# DRV8301_inverter.net
KiCad netlist of a schematic drawn in Altium Designer
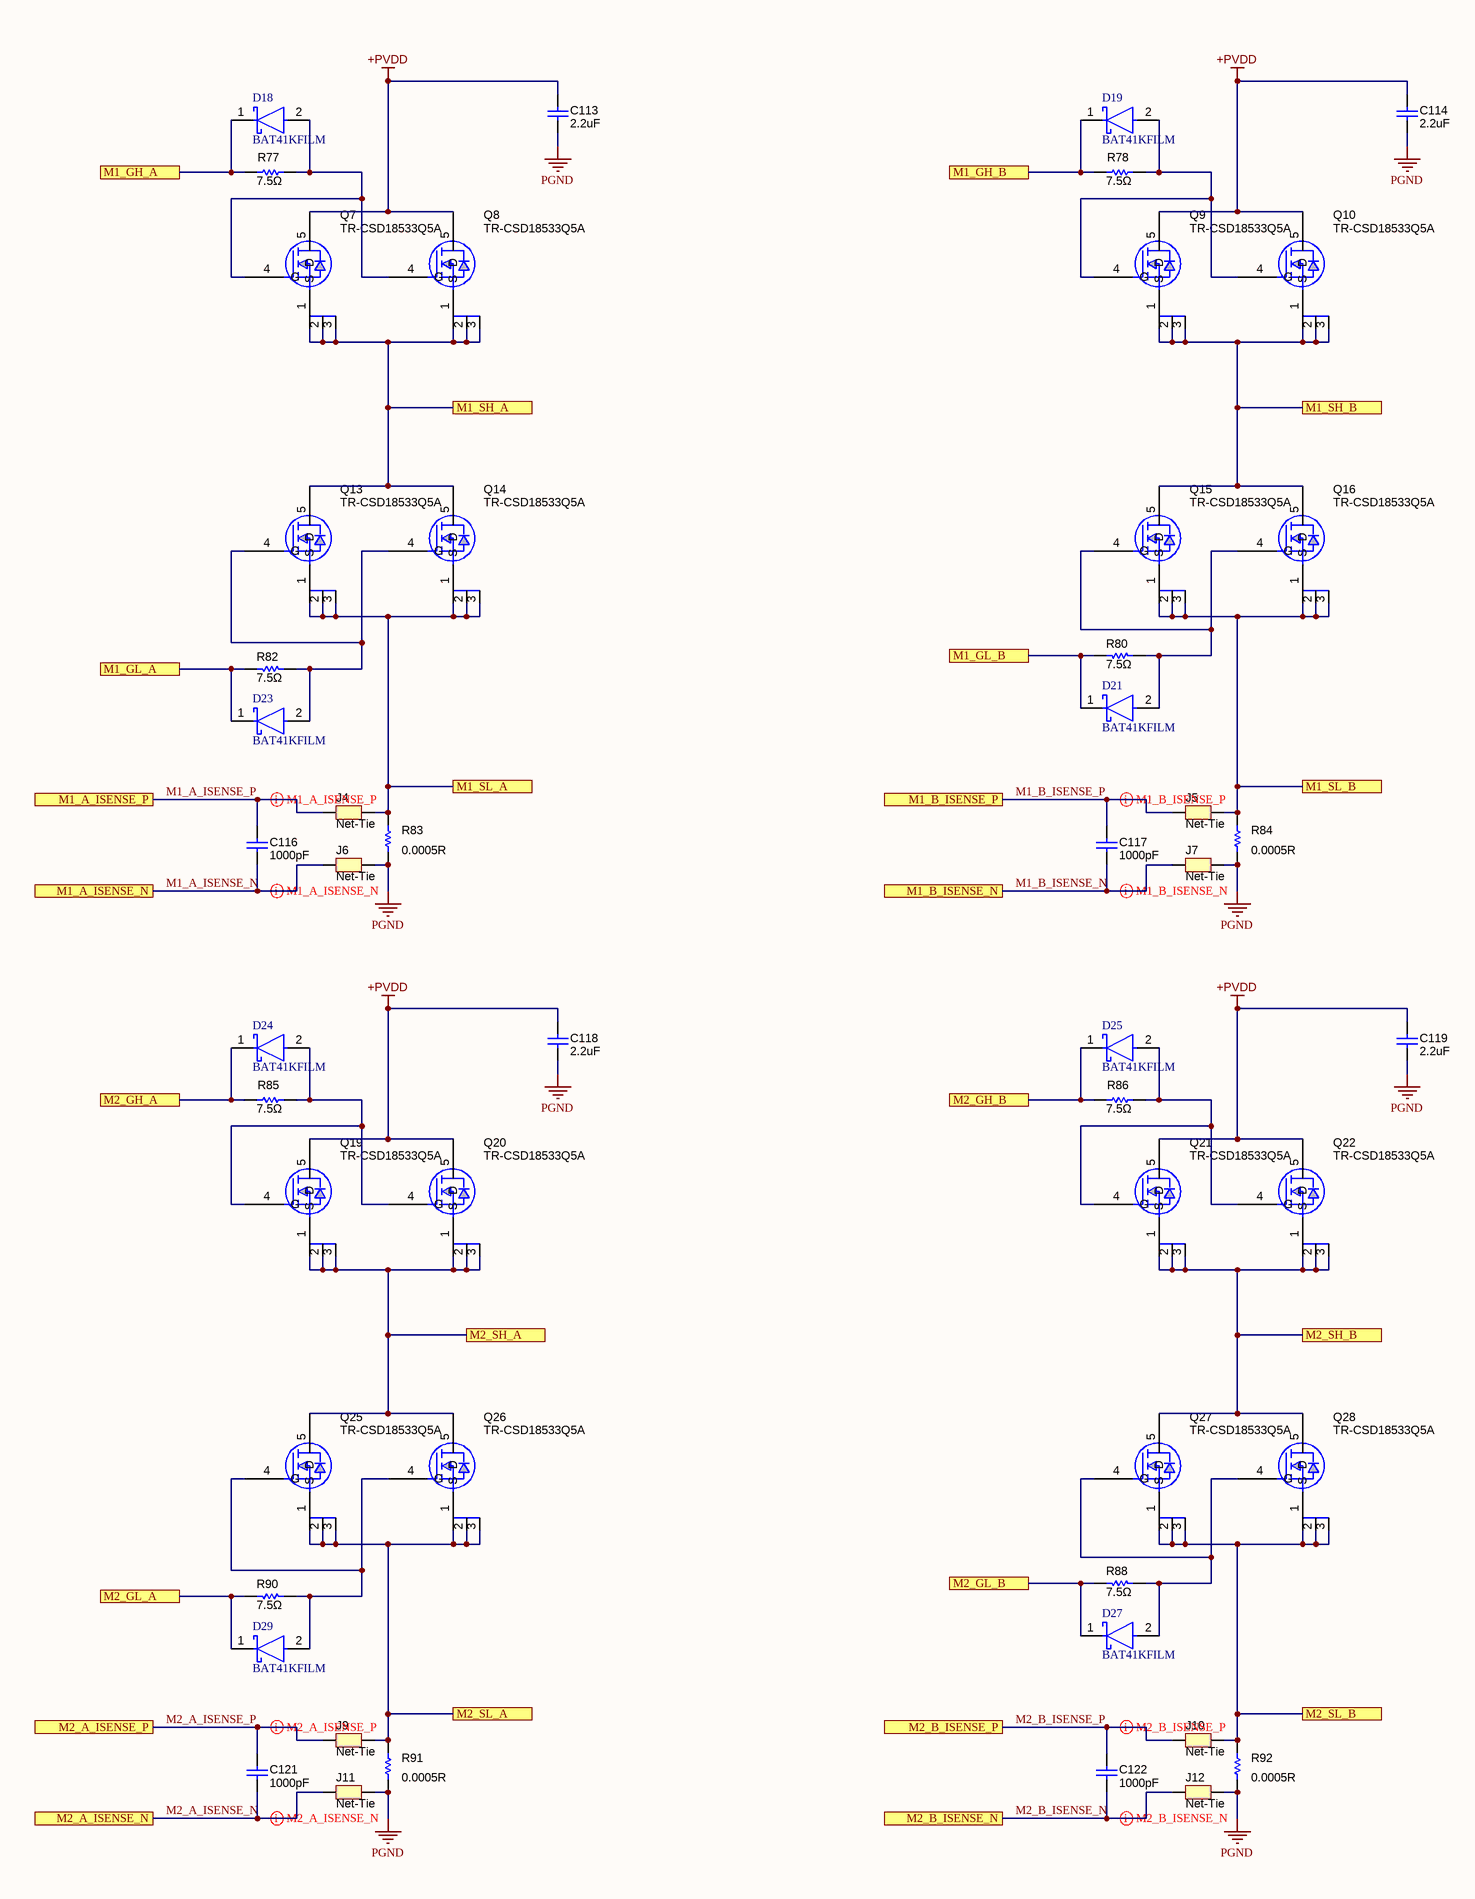
[diagram p0: DRV8301_inverter.SchDoc, left]
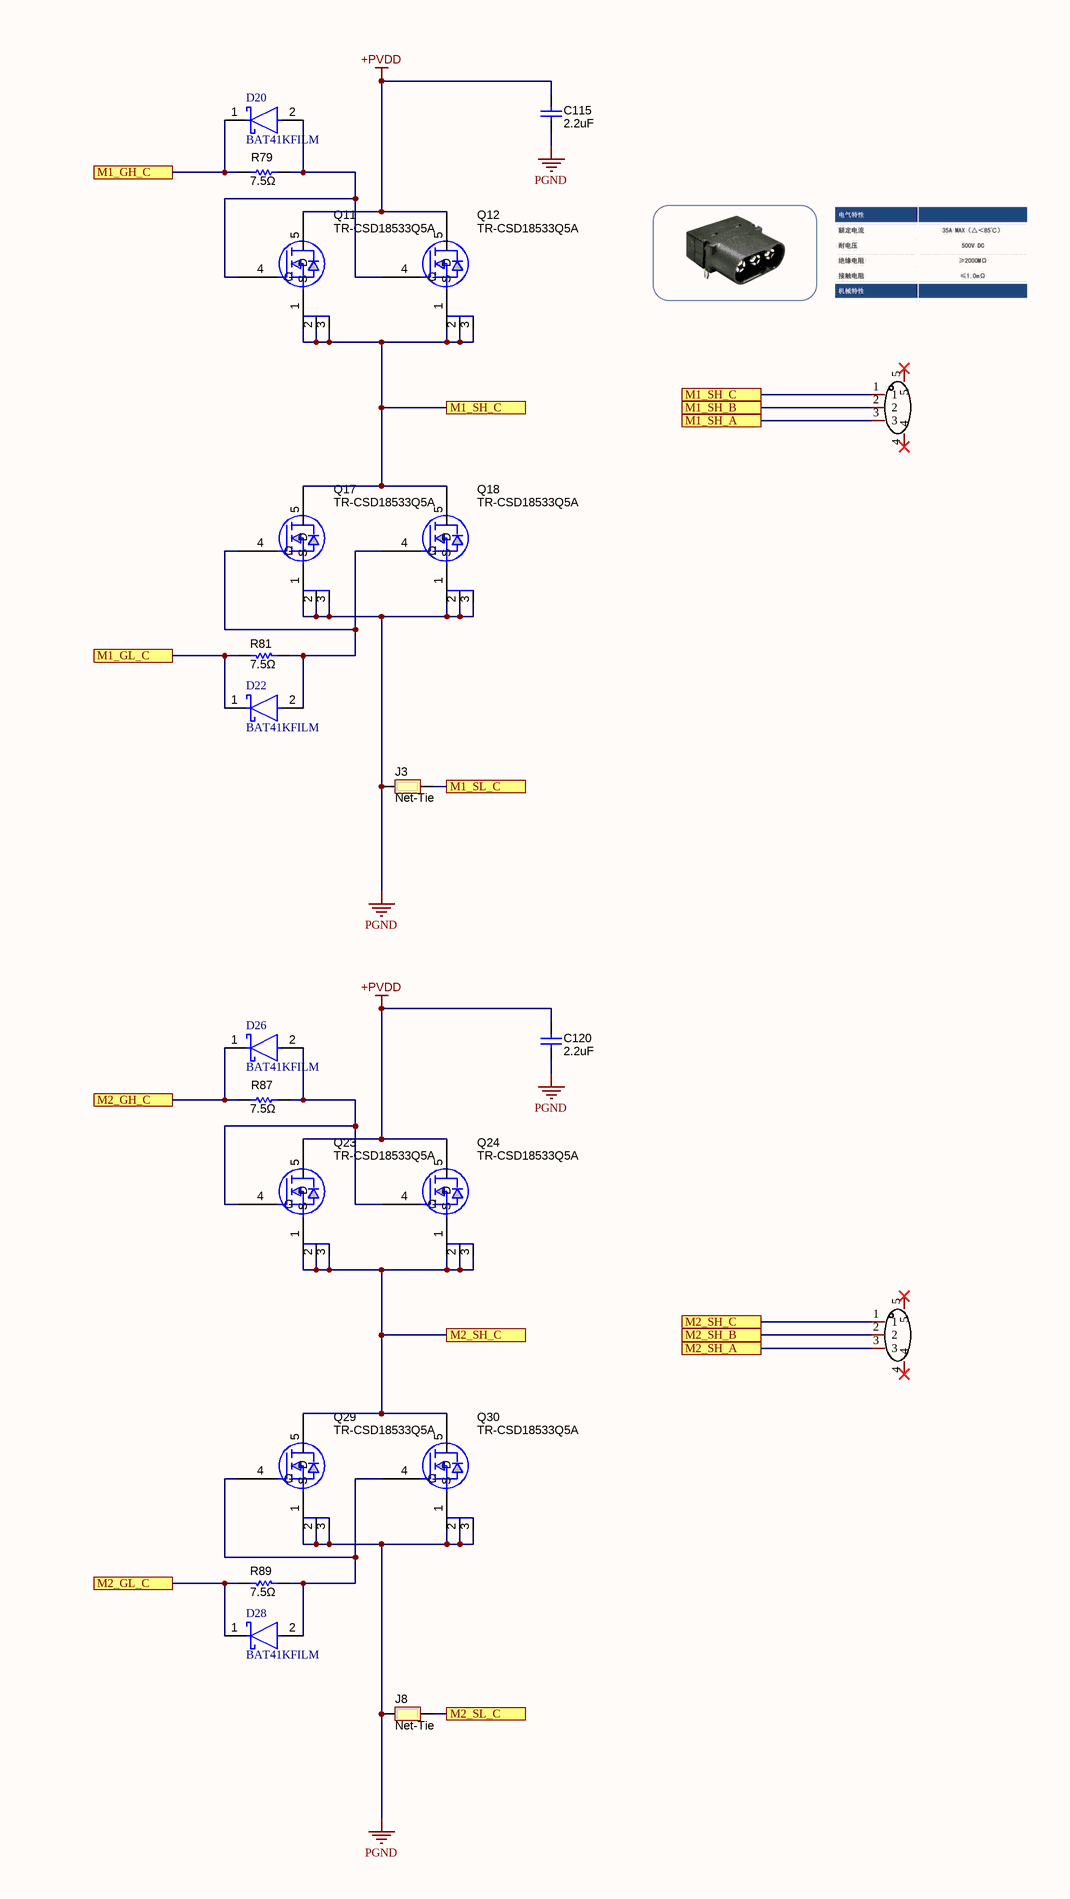
[diagram p1: DRV8301_inverter.SchDoc, right]

(export (version "E")
  (design (tool "Eeschema 10.0.6"))
  (components
    (comp (ref "C113")
      (value "GRM32ER72A225KA35L")
      (footprint "1210L")
      (description "CAP, CERM, 2.2uF, 100V, +/-10%, X7R, 1210")
      (fields
        (field (name "VALUEDISPLAYED") "2.2uF")
        (field (name "MANUFACTURER") "MuRata")
        (field (name "PUBLISHER") "Texas Instruments")
      )
      (libsource (lib "Capacitor_Ceramic") (part "GRM32ER72A225KA35L"))
    )
    (comp (ref "C114")
      (value "GRM32ER72A225KA35L")
      (footprint "1210L")
      (description "CAP, CERM, 2.2uF, 100V, +/-10%, X7R, 1210")
      (fields
        (field (name "VALUEDISPLAYED") "2.2uF")
        (field (name "MANUFACTURER") "MuRata")
        (field (name "PUBLISHER") "Texas Instruments")
      )
      (libsource (lib "Capacitor_Ceramic") (part "GRM32ER72A225KA35L"))
    )
    (comp (ref "C115")
      (value "GRM32ER72A225KA35L")
      (footprint "1210L")
      (description "CAP, CERM, 2.2uF, 100V, +/-10%, X7R, 1210")
      (fields
        (field (name "VALUEDISPLAYED") "2.2uF")
        (field (name "MANUFACTURER") "MuRata")
        (field (name "PUBLISHER") "Texas Instruments")
      )
      (libsource (lib "Capacitor_Ceramic") (part "GRM32ER72A225KA35L"))
    )
    (comp (ref "C116")
      (value "C0603C102J5GAC")
      (footprint "0603")
      (description "CAP, CERM, 1000pF, 50V, +/-5%, C0G/NP0, 0603")
      (fields
        (field (name "VALUEDISPLAYED") "1000pF")
        (field (name "MANUFACTURER") "Kemet")
        (field (name "PUBLISHER") "Texas Instruments")
      )
      (libsource (lib "Capacitor_Ceramic") (part "C0603C102J5GAC"))
    )
    (comp (ref "C117")
      (value "C0603C102J5GAC")
      (footprint "0603")
      (description "CAP, CERM, 1000pF, 50V, +/-5%, C0G/NP0, 0603")
      (fields
        (field (name "VALUEDISPLAYED") "1000pF")
        (field (name "MANUFACTURER") "Kemet")
        (field (name "PUBLISHER") "Texas Instruments")
      )
      (libsource (lib "Capacitor_Ceramic") (part "C0603C102J5GAC"))
    )
    (comp (ref "C118")
      (value "GRM32ER72A225KA35L")
      (footprint "1210L")
      (description "CAP, CERM, 2.2uF, 100V, +/-10%, X7R, 1210")
      (fields
        (field (name "VALUEDISPLAYED") "2.2uF")
        (field (name "MANUFACTURER") "MuRata")
        (field (name "PUBLISHER") "Texas Instruments")
      )
      (libsource (lib "Capacitor_Ceramic") (part "GRM32ER72A225KA35L"))
    )
    (comp (ref "C119")
      (value "GRM32ER72A225KA35L")
      (footprint "1210L")
      (description "CAP, CERM, 2.2uF, 100V, +/-10%, X7R, 1210")
      (fields
        (field (name "VALUEDISPLAYED") "2.2uF")
        (field (name "MANUFACTURER") "MuRata")
        (field (name "PUBLISHER") "Texas Instruments")
      )
      (libsource (lib "Capacitor_Ceramic") (part "GRM32ER72A225KA35L"))
    )
    (comp (ref "C120")
      (value "GRM32ER72A225KA35L")
      (footprint "1210L")
      (description "CAP, CERM, 2.2uF, 100V, +/-10%, X7R, 1210")
      (fields
        (field (name "VALUEDISPLAYED") "2.2uF")
        (field (name "MANUFACTURER") "MuRata")
        (field (name "PUBLISHER") "Texas Instruments")
      )
      (libsource (lib "Capacitor_Ceramic") (part "GRM32ER72A225KA35L"))
    )
    (comp (ref "C121")
      (value "C0603C102J5GAC")
      (footprint "0603")
      (description "CAP, CERM, 1000pF, 50V, +/-5%, C0G/NP0, 0603")
      (fields
        (field (name "VALUEDISPLAYED") "1000pF")
        (field (name "MANUFACTURER") "Kemet")
        (field (name "PUBLISHER") "Texas Instruments")
      )
      (libsource (lib "Capacitor_Ceramic") (part "C0603C102J5GAC"))
    )
    (comp (ref "C122")
      (value "C0603C102J5GAC")
      (footprint "0603")
      (description "CAP, CERM, 1000pF, 50V, +/-5%, C0G/NP0, 0603")
      (fields
        (field (name "VALUEDISPLAYED") "1000pF")
        (field (name "MANUFACTURER") "Kemet")
        (field (name "PUBLISHER") "Texas Instruments")
      )
      (libsource (lib "Capacitor_Ceramic") (part "C0603C102J5GAC"))
    )
    (comp (ref "D18")
      (value "BAT41KFILM")
      (footprint "FP-SOD-523-MFG")
      (description "DIODE SCHOTTKY 100V 200MA SOD523")
      (fields
        (field (name "OCTOPART") "https://octopart.com/bat41kfilm-stmicroelectronics-658186")
        (field (name "MANUFACTURER") "STMicroelectronics")
      )
      (libsource (lib "Altium Content Vault") (part "1d6ec82d83fb6aee721767c19dac4b9"))
    )
    (comp (ref "D19")
      (value "BAT41KFILM")
      (footprint "FP-SOD-523-MFG")
      (description "DIODE SCHOTTKY 100V 200MA SOD523")
      (fields
        (field (name "OCTOPART") "https://octopart.com/bat41kfilm-stmicroelectronics-658186")
        (field (name "MANUFACTURER") "STMicroelectronics")
      )
      (libsource (lib "Altium Content Vault") (part "1d6ec82d83fb6aee721767c19dac4b9"))
    )
    (comp (ref "D20")
      (value "BAT41KFILM")
      (footprint "FP-SOD-523-MFG")
      (description "DIODE SCHOTTKY 100V 200MA SOD523")
      (fields
        (field (name "OCTOPART") "https://octopart.com/bat41kfilm-stmicroelectronics-658186")
        (field (name "MANUFACTURER") "STMicroelectronics")
      )
      (libsource (lib "Altium Content Vault") (part "1d6ec82d83fb6aee721767c19dac4b9"))
    )
    (comp (ref "D21")
      (value "BAT41KFILM")
      (footprint "FP-SOD-523-MFG")
      (description "DIODE SCHOTTKY 100V 200MA SOD523")
      (fields
        (field (name "OCTOPART") "https://octopart.com/bat41kfilm-stmicroelectronics-658186")
        (field (name "MANUFACTURER") "STMicroelectronics")
      )
      (libsource (lib "Altium Content Vault") (part "1d6ec82d83fb6aee721767c19dac4b9"))
    )
    (comp (ref "D22")
      (value "BAT41KFILM")
      (footprint "FP-SOD-523-MFG")
      (description "DIODE SCHOTTKY 100V 200MA SOD523")
      (fields
        (field (name "OCTOPART") "https://octopart.com/bat41kfilm-stmicroelectronics-658186")
        (field (name "MANUFACTURER") "STMicroelectronics")
      )
      (libsource (lib "Altium Content Vault") (part "1d6ec82d83fb6aee721767c19dac4b9"))
    )
    (comp (ref "D23")
      (value "BAT41KFILM")
      (footprint "FP-SOD-523-MFG")
      (description "DIODE SCHOTTKY 100V 200MA SOD523")
      (fields
        (field (name "OCTOPART") "https://octopart.com/bat41kfilm-stmicroelectronics-658186")
        (field (name "MANUFACTURER") "STMicroelectronics")
      )
      (libsource (lib "Altium Content Vault") (part "1d6ec82d83fb6aee721767c19dac4b9"))
    )
    (comp (ref "D24")
      (value "BAT41KFILM")
      (footprint "FP-SOD-523-MFG")
      (description "DIODE SCHOTTKY 100V 200MA SOD523")
      (fields
        (field (name "OCTOPART") "https://octopart.com/bat41kfilm-stmicroelectronics-658186")
        (field (name "MANUFACTURER") "STMicroelectronics")
      )
      (libsource (lib "Altium Content Vault") (part "1d6ec82d83fb6aee721767c19dac4b9"))
    )
    (comp (ref "D25")
      (value "BAT41KFILM")
      (footprint "FP-SOD-523-MFG")
      (description "DIODE SCHOTTKY 100V 200MA SOD523")
      (fields
        (field (name "OCTOPART") "https://octopart.com/bat41kfilm-stmicroelectronics-658186")
        (field (name "MANUFACTURER") "STMicroelectronics")
      )
      (libsource (lib "Altium Content Vault") (part "1d6ec82d83fb6aee721767c19dac4b9"))
    )
    (comp (ref "D26")
      (value "BAT41KFILM")
      (footprint "FP-SOD-523-MFG")
      (description "DIODE SCHOTTKY 100V 200MA SOD523")
      (fields
        (field (name "OCTOPART") "https://octopart.com/bat41kfilm-stmicroelectronics-658186")
        (field (name "MANUFACTURER") "STMicroelectronics")
      )
      (libsource (lib "Altium Content Vault") (part "1d6ec82d83fb6aee721767c19dac4b9"))
    )
    (comp (ref "D27")
      (value "BAT41KFILM")
      (footprint "FP-SOD-523-MFG")
      (description "DIODE SCHOTTKY 100V 200MA SOD523")
      (fields
        (field (name "OCTOPART") "https://octopart.com/bat41kfilm-stmicroelectronics-658186")
        (field (name "MANUFACTURER") "STMicroelectronics")
      )
      (libsource (lib "Altium Content Vault") (part "1d6ec82d83fb6aee721767c19dac4b9"))
    )
    (comp (ref "D28")
      (value "BAT41KFILM")
      (footprint "FP-SOD-523-MFG")
      (description "DIODE SCHOTTKY 100V 200MA SOD523")
      (fields
        (field (name "OCTOPART") "https://octopart.com/bat41kfilm-stmicroelectronics-658186")
        (field (name "MANUFACTURER") "STMicroelectronics")
      )
      (libsource (lib "Altium Content Vault") (part "1d6ec82d83fb6aee721767c19dac4b9"))
    )
    (comp (ref "D29")
      (value "BAT41KFILM")
      (footprint "FP-SOD-523-MFG")
      (description "DIODE SCHOTTKY 100V 200MA SOD523")
      (fields
        (field (name "OCTOPART") "https://octopart.com/bat41kfilm-stmicroelectronics-658186")
        (field (name "MANUFACTURER") "STMicroelectronics")
      )
      (libsource (lib "Altium Content Vault") (part "1d6ec82d83fb6aee721767c19dac4b9"))
    )
    (comp (ref "J3")
      (value "Net-Tie")
      (footprint "Net-Tie_10mil")
      (description "Single point connection between nets.")
      (fields (field (name "SYMBOLCREATOR") "codlsc") (field (name "PUBLISHER") "Texas Instruments"))
      (libsource (lib "MiscParts") (part "Net-Tie"))
    )
    (comp (ref "J4")
      (value "Net-Tie")
      (footprint "Net-Tie_10mil")
      (description "Single point connection between nets.")
      (fields (field (name "SYMBOLCREATOR") "codlsc") (field (name "PUBLISHER") "Texas Instruments"))
      (libsource (lib "MiscParts") (part "Net-Tie"))
    )
    (comp (ref "J5")
      (value "Net-Tie")
      (footprint "Net-Tie_10mil")
      (description "Single point connection between nets.")
      (fields (field (name "SYMBOLCREATOR") "codlsc") (field (name "PUBLISHER") "Texas Instruments"))
      (libsource (lib "MiscParts") (part "Net-Tie"))
    )
    (comp (ref "J6")
      (value "Net-Tie")
      (footprint "Net-Tie_10mil")
      (description "Single point connection between nets.")
      (fields (field (name "SYMBOLCREATOR") "codlsc") (field (name "PUBLISHER") "Texas Instruments"))
      (libsource (lib "MiscParts") (part "Net-Tie"))
    )
    (comp (ref "J7")
      (value "Net-Tie")
      (footprint "Net-Tie_10mil")
      (description "Single point connection between nets.")
      (fields (field (name "SYMBOLCREATOR") "codlsc") (field (name "PUBLISHER") "Texas Instruments"))
      (libsource (lib "MiscParts") (part "Net-Tie"))
    )
    (comp (ref "J8")
      (value "Net-Tie")
      (footprint "Net-Tie_10mil")
      (description "Single point connection between nets.")
      (fields (field (name "SYMBOLCREATOR") "codlsc") (field (name "PUBLISHER") "Texas Instruments"))
      (libsource (lib "MiscParts") (part "Net-Tie"))
    )
    (comp (ref "J9")
      (value "Net-Tie")
      (footprint "Net-Tie_10mil")
      (description "Single point connection between nets.")
      (fields (field (name "SYMBOLCREATOR") "codlsc") (field (name "PUBLISHER") "Texas Instruments"))
      (libsource (lib "MiscParts") (part "Net-Tie"))
    )
    (comp (ref "J10")
      (value "Net-Tie")
      (footprint "Net-Tie_10mil")
      (description "Single point connection between nets.")
      (fields (field (name "SYMBOLCREATOR") "codlsc") (field (name "PUBLISHER") "Texas Instruments"))
      (libsource (lib "MiscParts") (part "Net-Tie"))
    )
    (comp (ref "J11")
      (value "Net-Tie")
      (footprint "Net-Tie_10mil")
      (description "Single point connection between nets.")
      (fields (field (name "SYMBOLCREATOR") "codlsc") (field (name "PUBLISHER") "Texas Instruments"))
      (libsource (lib "MiscParts") (part "Net-Tie"))
    )
    (comp (ref "J12")
      (value "Net-Tie")
      (footprint "Net-Tie_10mil")
      (description "Single point connection between nets.")
      (fields (field (name "SYMBOLCREATOR") "codlsc") (field (name "PUBLISHER") "Texas Instruments"))
      (libsource (lib "MiscParts") (part "Net-Tie"))
    )
    (comp (ref "Q7")
      (value "TR-CSD18533Q5A")
      (footprint "QFN5X6MM")
      (description "MOSFET, N-Chan, 60V, 18A, 6.1 mOhm")
      (fields (field (name "MANUFACTURER") "TI") (field (name "PARTNUMBER") "CSD18533Q5A"))
      (libsource (lib "PADSlegacy_Active") (part "TR-CSD18533Q5A"))
    )
    (comp (ref "Q8")
      (value "TR-CSD18533Q5A")
      (footprint "QFN5X6MM")
      (description "MOSFET, N-Chan, 60V, 18A, 6.1 mOhm")
      (fields (field (name "MANUFACTURER") "TI") (field (name "PARTNUMBER") "CSD18533Q5A"))
      (libsource (lib "PADSlegacy_Active") (part "TR-CSD18533Q5A"))
    )
    (comp (ref "Q9")
      (value "TR-CSD18533Q5A")
      (footprint "QFN5X6MM")
      (description "MOSFET, N-Chan, 60V, 18A, 6.1 mOhm")
      (fields (field (name "MANUFACTURER") "TI") (field (name "PARTNUMBER") "CSD18533Q5A"))
      (libsource (lib "PADSlegacy_Active") (part "TR-CSD18533Q5A"))
    )
    (comp (ref "Q10")
      (value "TR-CSD18533Q5A")
      (footprint "QFN5X6MM")
      (description "MOSFET, N-Chan, 60V, 18A, 6.1 mOhm")
      (fields (field (name "MANUFACTURER") "TI") (field (name "PARTNUMBER") "CSD18533Q5A"))
      (libsource (lib "PADSlegacy_Active") (part "TR-CSD18533Q5A"))
    )
    (comp (ref "Q11")
      (value "TR-CSD18533Q5A")
      (footprint "QFN5X6MM")
      (description "MOSFET, N-Chan, 60V, 18A, 6.1 mOhm")
      (fields (field (name "MANUFACTURER") "TI") (field (name "PARTNUMBER") "CSD18533Q5A"))
      (libsource (lib "PADSlegacy_Active") (part "TR-CSD18533Q5A"))
    )
    (comp (ref "Q12")
      (value "TR-CSD18533Q5A")
      (footprint "QFN5X6MM")
      (description "MOSFET, N-Chan, 60V, 18A, 6.1 mOhm")
      (fields (field (name "MANUFACTURER") "TI") (field (name "PARTNUMBER") "CSD18533Q5A"))
      (libsource (lib "PADSlegacy_Active") (part "TR-CSD18533Q5A"))
    )
    (comp (ref "Q13")
      (value "TR-CSD18533Q5A")
      (footprint "QFN5X6MM")
      (description "MOSFET, N-Chan, 60V, 18A, 6.1 mOhm")
      (fields (field (name "MANUFACTURER") "TI") (field (name "PARTNUMBER") "CSD18533Q5A"))
      (libsource (lib "PADSlegacy_Active") (part "TR-CSD18533Q5A"))
    )
    (comp (ref "Q14")
      (value "TR-CSD18533Q5A")
      (footprint "QFN5X6MM")
      (description "MOSFET, N-Chan, 60V, 18A, 6.1 mOhm")
      (fields (field (name "MANUFACTURER") "TI") (field (name "PARTNUMBER") "CSD18533Q5A"))
      (libsource (lib "PADSlegacy_Active") (part "TR-CSD18533Q5A"))
    )
    (comp (ref "Q15")
      (value "TR-CSD18533Q5A")
      (footprint "QFN5X6MM")
      (description "MOSFET, N-Chan, 60V, 18A, 6.1 mOhm")
      (fields (field (name "MANUFACTURER") "TI") (field (name "PARTNUMBER") "CSD18533Q5A"))
      (libsource (lib "PADSlegacy_Active") (part "TR-CSD18533Q5A"))
    )
    (comp (ref "Q16")
      (value "TR-CSD18533Q5A")
      (footprint "QFN5X6MM")
      (description "MOSFET, N-Chan, 60V, 18A, 6.1 mOhm")
      (fields (field (name "MANUFACTURER") "TI") (field (name "PARTNUMBER") "CSD18533Q5A"))
      (libsource (lib "PADSlegacy_Active") (part "TR-CSD18533Q5A"))
    )
    (comp (ref "Q17")
      (value "TR-CSD18533Q5A")
      (footprint "QFN5X6MM")
      (description "MOSFET, N-Chan, 60V, 18A, 6.1 mOhm")
      (fields (field (name "MANUFACTURER") "TI") (field (name "PARTNUMBER") "CSD18533Q5A"))
      (libsource (lib "PADSlegacy_Active") (part "TR-CSD18533Q5A"))
    )
    (comp (ref "Q18")
      (value "TR-CSD18533Q5A")
      (footprint "QFN5X6MM")
      (description "MOSFET, N-Chan, 60V, 18A, 6.1 mOhm")
      (fields (field (name "MANUFACTURER") "TI") (field (name "PARTNUMBER") "CSD18533Q5A"))
      (libsource (lib "PADSlegacy_Active") (part "TR-CSD18533Q5A"))
    )
    (comp (ref "Q19")
      (value "TR-CSD18533Q5A")
      (footprint "QFN5X6MM")
      (description "MOSFET, N-Chan, 60V, 18A, 6.1 mOhm")
      (fields (field (name "MANUFACTURER") "TI") (field (name "PARTNUMBER") "CSD18533Q5A"))
      (libsource (lib "PADSlegacy_Active") (part "TR-CSD18533Q5A"))
    )
    (comp (ref "Q20")
      (value "TR-CSD18533Q5A")
      (footprint "QFN5X6MM")
      (description "MOSFET, N-Chan, 60V, 18A, 6.1 mOhm")
      (fields (field (name "MANUFACTURER") "TI") (field (name "PARTNUMBER") "CSD18533Q5A"))
      (libsource (lib "PADSlegacy_Active") (part "TR-CSD18533Q5A"))
    )
    (comp (ref "Q21")
      (value "TR-CSD18533Q5A")
      (footprint "QFN5X6MM")
      (description "MOSFET, N-Chan, 60V, 18A, 6.1 mOhm")
      (fields (field (name "MANUFACTURER") "TI") (field (name "PARTNUMBER") "CSD18533Q5A"))
      (libsource (lib "PADSlegacy_Active") (part "TR-CSD18533Q5A"))
    )
    (comp (ref "Q22")
      (value "TR-CSD18533Q5A")
      (footprint "QFN5X6MM")
      (description "MOSFET, N-Chan, 60V, 18A, 6.1 mOhm")
      (fields (field (name "MANUFACTURER") "TI") (field (name "PARTNUMBER") "CSD18533Q5A"))
      (libsource (lib "PADSlegacy_Active") (part "TR-CSD18533Q5A"))
    )
    (comp (ref "Q23")
      (value "TR-CSD18533Q5A")
      (footprint "QFN5X6MM")
      (description "MOSFET, N-Chan, 60V, 18A, 6.1 mOhm")
      (fields (field (name "MANUFACTURER") "TI") (field (name "PARTNUMBER") "CSD18533Q5A"))
      (libsource (lib "PADSlegacy_Active") (part "TR-CSD18533Q5A"))
    )
    (comp (ref "Q24")
      (value "TR-CSD18533Q5A")
      (footprint "QFN5X6MM")
      (description "MOSFET, N-Chan, 60V, 18A, 6.1 mOhm")
      (fields (field (name "MANUFACTURER") "TI") (field (name "PARTNUMBER") "CSD18533Q5A"))
      (libsource (lib "PADSlegacy_Active") (part "TR-CSD18533Q5A"))
    )
    (comp (ref "Q25")
      (value "TR-CSD18533Q5A")
      (footprint "QFN5X6MM")
      (description "MOSFET, N-Chan, 60V, 18A, 6.1 mOhm")
      (fields (field (name "MANUFACTURER") "TI") (field (name "PARTNUMBER") "CSD18533Q5A"))
      (libsource (lib "PADSlegacy_Active") (part "TR-CSD18533Q5A"))
    )
    (comp (ref "Q26")
      (value "TR-CSD18533Q5A")
      (footprint "QFN5X6MM")
      (description "MOSFET, N-Chan, 60V, 18A, 6.1 mOhm")
      (fields (field (name "MANUFACTURER") "TI") (field (name "PARTNUMBER") "CSD18533Q5A"))
      (libsource (lib "PADSlegacy_Active") (part "TR-CSD18533Q5A"))
    )
    (comp (ref "Q27")
      (value "TR-CSD18533Q5A")
      (footprint "QFN5X6MM")
      (description "MOSFET, N-Chan, 60V, 18A, 6.1 mOhm")
      (fields (field (name "MANUFACTURER") "TI") (field (name "PARTNUMBER") "CSD18533Q5A"))
      (libsource (lib "PADSlegacy_Active") (part "TR-CSD18533Q5A"))
    )
    (comp (ref "Q28")
      (value "TR-CSD18533Q5A")
      (footprint "QFN5X6MM")
      (description "MOSFET, N-Chan, 60V, 18A, 6.1 mOhm")
      (fields (field (name "MANUFACTURER") "TI") (field (name "PARTNUMBER") "CSD18533Q5A"))
      (libsource (lib "PADSlegacy_Active") (part "TR-CSD18533Q5A"))
    )
    (comp (ref "Q29")
      (value "TR-CSD18533Q5A")
      (footprint "QFN5X6MM")
      (description "MOSFET, N-Chan, 60V, 18A, 6.1 mOhm")
      (fields (field (name "MANUFACTURER") "TI") (field (name "PARTNUMBER") "CSD18533Q5A"))
      (libsource (lib "PADSlegacy_Active") (part "TR-CSD18533Q5A"))
    )
    (comp (ref "Q30")
      (value "TR-CSD18533Q5A")
      (footprint "QFN5X6MM")
      (description "MOSFET, N-Chan, 60V, 18A, 6.1 mOhm")
      (fields (field (name "MANUFACTURER") "TI") (field (name "PARTNUMBER") "CSD18533Q5A"))
      (libsource (lib "PADSlegacy_Active") (part "TR-CSD18533Q5A"))
    )
    (comp (ref "R77")
      (value "7.5Ω")
      (footprint "0603L")
      (description "RES, 7.5 ohm, 5%, 0.1W, 0603")
      (fields
        (field (name "PARTNUMBER") "CRCW060310R0JNEA")
        (field (name "MANUFACTURER") "Vishay-Dale")
        (field (name "PUBLISHER") "Texas Instruments")
      )
      (libsource (lib "Resistor_0603") (part "CRCW060310R0JNEA"))
    )
    (comp (ref "R78")
      (value "7.5Ω")
      (footprint "0603L")
      (description "RES, 7.5 ohm, 5%, 0.1W, 0603")
      (fields
        (field (name "PARTNUMBER") "CRCW060310R0JNEA")
        (field (name "MANUFACTURER") "Vishay-Dale")
        (field (name "PUBLISHER") "Texas Instruments")
      )
      (libsource (lib "Resistor_0603") (part "CRCW060310R0JNEA"))
    )
    (comp (ref "R79")
      (value "7.5Ω")
      (footprint "0603L")
      (description "RES, 7.5 ohm, 5%, 0.1W, 0603")
      (fields
        (field (name "PARTNUMBER") "CRCW060310R0JNEA")
        (field (name "MANUFACTURER") "Vishay-Dale")
        (field (name "PUBLISHER") "Texas Instruments")
      )
      (libsource (lib "Resistor_0603") (part "CRCW060310R0JNEA"))
    )
    (comp (ref "R80")
      (value "7.5Ω")
      (footprint "0603L")
      (description "RES, 7.5 ohm, 5%, 0.1W, 0603")
      (fields
        (field (name "PARTNUMBER") "CRCW060310R0JNEA")
        (field (name "MANUFACTURER") "Vishay-Dale")
        (field (name "PUBLISHER") "Texas Instruments")
      )
      (libsource (lib "Resistor_0603") (part "CRCW060310R0JNEA"))
    )
    (comp (ref "R81")
      (value "7.5Ω")
      (footprint "0603L")
      (description "RES, 7.5 ohm, 5%, 0.1W, 0603")
      (fields
        (field (name "PARTNUMBER") "CRCW060310R0JNEA")
        (field (name "MANUFACTURER") "Vishay-Dale")
        (field (name "PUBLISHER") "Texas Instruments")
      )
      (libsource (lib "Resistor_0603") (part "CRCW060310R0JNEA"))
    )
    (comp (ref "R82")
      (value "7.5Ω")
      (footprint "0603L")
      (description "RES, 7.5 ohm, 5%, 0.1W, 0603")
      (fields
        (field (name "PARTNUMBER") "CRCW060310R0JNEA")
        (field (name "MANUFACTURER") "Vishay-Dale")
        (field (name "PUBLISHER") "Texas Instruments")
      )
      (libsource (lib "Resistor_0603") (part "CRCW060310R0JNEA"))
    )
    (comp (ref "R83")
      (value "0.0005R")
      (footprint "2512M")
      (description "RES, 0.01 ohm, 1%, 3W, 2512")
      (fields
        (field (name "PARTNUMBER") "CRA2512-FZ-R010ELF")
        (field (name "MANUFACTURER") "Bourns")
        (field (name "PUBLISHER") "Texas Instruments")
      )
      (libsource (lib "Resistor_OtherSMT") (part "CRA2512-FZ-R010ELF"))
    )
    (comp (ref "R84")
      (value "0.0005R")
      (footprint "2512M")
      (description "RES, 0.01 ohm, 1%, 3W, 2512")
      (fields
        (field (name "PARTNUMBER") "CRA2512-FZ-R010ELF")
        (field (name "MANUFACTURER") "Bourns")
        (field (name "PUBLISHER") "Texas Instruments")
      )
      (libsource (lib "Resistor_OtherSMT") (part "CRA2512-FZ-R010ELF"))
    )
    (comp (ref "R85")
      (value "7.5Ω")
      (footprint "0603L")
      (description "RES, 7.5 ohm, 5%, 0.1W, 0603")
      (fields
        (field (name "PARTNUMBER") "CRCW060310R0JNEA")
        (field (name "MANUFACTURER") "Vishay-Dale")
        (field (name "PUBLISHER") "Texas Instruments")
      )
      (libsource (lib "Resistor_0603") (part "CRCW060310R0JNEA"))
    )
    (comp (ref "R86")
      (value "7.5Ω")
      (footprint "0603L")
      (description "RES, 7.5 ohm, 5%, 0.1W, 0603")
      (fields
        (field (name "PARTNUMBER") "CRCW060310R0JNEA")
        (field (name "MANUFACTURER") "Vishay-Dale")
        (field (name "PUBLISHER") "Texas Instruments")
      )
      (libsource (lib "Resistor_0603") (part "CRCW060310R0JNEA"))
    )
    (comp (ref "R87")
      (value "7.5Ω")
      (footprint "0603L")
      (description "RES, 7.5 ohm, 5%, 0.1W, 0603")
      (fields
        (field (name "PARTNUMBER") "CRCW060310R0JNEA")
        (field (name "MANUFACTURER") "Vishay-Dale")
        (field (name "PUBLISHER") "Texas Instruments")
      )
      (libsource (lib "Resistor_0603") (part "CRCW060310R0JNEA"))
    )
    (comp (ref "R88")
      (value "7.5Ω")
      (footprint "0603L")
      (description "RES, 7.5 ohm, 5%, 0.1W, 0603")
      (fields
        (field (name "PARTNUMBER") "CRCW060310R0JNEA")
        (field (name "MANUFACTURER") "Vishay-Dale")
        (field (name "PUBLISHER") "Texas Instruments")
      )
      (libsource (lib "Resistor_0603") (part "CRCW060310R0JNEA"))
    )
    (comp (ref "R89")
      (value "7.5Ω")
      (footprint "0603L")
      (description "RES, 7.5 ohm, 5%, 0.1W, 0603")
      (fields
        (field (name "PARTNUMBER") "CRCW060310R0JNEA")
        (field (name "MANUFACTURER") "Vishay-Dale")
        (field (name "PUBLISHER") "Texas Instruments")
      )
      (libsource (lib "Resistor_0603") (part "CRCW060310R0JNEA"))
    )
    (comp (ref "R90")
      (value "7.5Ω")
      (footprint "0603L")
      (description "RES, 7.5 ohm, 5%, 0.1W, 0603")
      (fields
        (field (name "PARTNUMBER") "CRCW060310R0JNEA")
        (field (name "MANUFACTURER") "Vishay-Dale")
        (field (name "PUBLISHER") "Texas Instruments")
      )
      (libsource (lib "Resistor_0603") (part "CRCW060310R0JNEA"))
    )
    (comp (ref "R91")
      (value "0.0005R")
      (footprint "2512M")
      (description "RES, 0.01 ohm, 1%, 3W, 2512")
      (fields
        (field (name "PARTNUMBER") "CRA2512-FZ-R010ELF")
        (field (name "MANUFACTURER") "Bourns")
        (field (name "PUBLISHER") "Texas Instruments")
      )
      (libsource (lib "Resistor_OtherSMT") (part "CRA2512-FZ-R010ELF"))
    )
    (comp (ref "R92")
      (value "0.0005R")
      (footprint "2512M")
      (description "RES, 0.01 ohm, 1%, 3W, 2512")
      (fields
        (field (name "PARTNUMBER") "CRA2512-FZ-R010ELF")
        (field (name "MANUFACTURER") "Bourns")
        (field (name "PUBLISHER") "Texas Instruments")
      )
      (libsource (lib "Resistor_OtherSMT") (part "CRA2512-FZ-R010ELF"))
    )
    (comp (ref "U25")
      (value "MR60PW-M.G.B")
      (footprint "CONN-TH_MR60PW")
      (fields (field (name "MANUFACTURER") "AMASS(艾迈斯)"))
      (libsource (lib "two_ax_PCB") (part "MR60PW-M.G.B"))
    )
    (comp (ref "U26")
      (value "MR60PW-M.G.B")
      (footprint "CONN-TH_MR60PW")
      (fields (field (name "MANUFACTURER") "AMASS(艾迈斯)"))
      (libsource (lib "two_ax_PCB") (part "MR60PW-M.G.B"))
    )
  )
  (nets
    (net (code "1") (name "+PVDD") (class "Default")
      (node (ref "C113") (pin "1") (pinfunction "1_1") (pintype "passive"))
      (node (ref "C114") (pin "1") (pinfunction "1_1") (pintype "passive"))
      (node (ref "C115") (pin "1") (pinfunction "1_1") (pintype "passive"))
      (node (ref "C118") (pin "1") (pinfunction "1_1") (pintype "passive"))
      (node (ref "C119") (pin "1") (pinfunction "1_1") (pintype "passive"))
      (node (ref "C120") (pin "1") (pinfunction "1_1") (pintype "passive"))
      (node (ref "Q10") (pin "5") (pinfunction "D_5") (pintype "passive"))
      (node (ref "Q11") (pin "5") (pinfunction "D_5") (pintype "passive"))
      (node (ref "Q12") (pin "5") (pinfunction "D_5") (pintype "passive"))
      (node (ref "Q19") (pin "5") (pinfunction "D_5") (pintype "passive"))
      (node (ref "Q20") (pin "5") (pinfunction "D_5") (pintype "passive"))
      (node (ref "Q21") (pin "5") (pinfunction "D_5") (pintype "passive"))
      (node (ref "Q22") (pin "5") (pinfunction "D_5") (pintype "passive"))
      (node (ref "Q23") (pin "5") (pinfunction "D_5") (pintype "passive"))
      (node (ref "Q24") (pin "5") (pinfunction "D_5") (pintype "passive"))
      (node (ref "Q7") (pin "5") (pinfunction "D_5") (pintype "passive"))
      (node (ref "Q8") (pin "5") (pinfunction "D_5") (pintype "passive"))
      (node (ref "Q9") (pin "5") (pinfunction "D_5") (pintype "passive"))
    )
    (net (code "2") (name "/M1_A_ISENSE_N") (class "Default")
      (node (ref "C116") (pin "2") (pinfunction "2_2") (pintype "passive"))
      (node (ref "J6") (pin "2") (pinfunction "2_2") (pintype "passive"))
    )
    (net (code "3") (name "/M1_A_ISENSE_P") (class "Default")
      (node (ref "C116") (pin "1") (pinfunction "1_1") (pintype "passive"))
      (node (ref "J4") (pin "2") (pinfunction "2_2") (pintype "passive"))
    )
    (net (code "4") (name "/M1_B_ISENSE_N") (class "Default")
      (node (ref "C117") (pin "2") (pinfunction "2_2") (pintype "passive"))
      (node (ref "J7") (pin "2") (pinfunction "2_2") (pintype "passive"))
    )
    (net (code "5") (name "/M1_B_ISENSE_P") (class "Default")
      (node (ref "C117") (pin "1") (pinfunction "1_1") (pintype "passive"))
      (node (ref "J5") (pin "2") (pinfunction "2_2") (pintype "passive"))
    )
    (net (code "6") (name "/M1_GH_A") (class "Default")
      (node (ref "D18") (pin "1") (pinfunction "C_1") (pintype "passive"))
      (node (ref "R77") (pin "1") (pinfunction "1_1") (pintype "passive"))
    )
    (net (code "7") (name "/M1_GH_B") (class "Default")
      (node (ref "D19") (pin "1") (pinfunction "C_1") (pintype "passive"))
      (node (ref "R78") (pin "1") (pinfunction "1_1") (pintype "passive"))
    )
    (net (code "8") (name "/M1_GH_C") (class "Default")
      (node (ref "D20") (pin "1") (pinfunction "C_1") (pintype "passive"))
      (node (ref "R79") (pin "1") (pinfunction "1_1") (pintype "passive"))
    )
    (net (code "9") (name "/M1_GL_A") (class "Default")
      (node (ref "D23") (pin "1") (pinfunction "C_1") (pintype "passive"))
      (node (ref "R82") (pin "1") (pinfunction "1_1") (pintype "passive"))
    )
    (net (code "10") (name "/M1_GL_B") (class "Default")
      (node (ref "D21") (pin "1") (pinfunction "C_1") (pintype "passive"))
      (node (ref "R80") (pin "1") (pinfunction "1_1") (pintype "passive"))
    )
    (net (code "11") (name "/M1_GL_C") (class "Default")
      (node (ref "D22") (pin "1") (pinfunction "C_1") (pintype "passive"))
      (node (ref "R81") (pin "1") (pinfunction "1_1") (pintype "passive"))
    )
    (net (code "12") (name "/M1_SH_A") (class "Default")
      (node (ref "Q13") (pin "5") (pinfunction "D_5") (pintype "passive"))
      (node (ref "Q14") (pin "5") (pinfunction "D_5") (pintype "passive"))
      (node (ref "Q7") (pin "1") (pinfunction "S_1") (pintype "passive"))
      (node (ref "Q7") (pin "2") (pintype "passive"))
      (node (ref "Q7") (pin "3") (pintype "passive"))
      (node (ref "Q8") (pin "1") (pinfunction "S_1") (pintype "passive"))
      (node (ref "Q8") (pin "2") (pintype "passive"))
      (node (ref "Q8") (pin "3") (pintype "passive"))
      (node (ref "U25") (pin "3") (pinfunction "3_3") (pintype "passive"))
    )
    (net (code "13") (name "/M1_SH_B") (class "Default")
      (node (ref "Q10") (pin "1") (pinfunction "S_1") (pintype "passive"))
      (node (ref "Q10") (pin "2") (pintype "passive"))
      (node (ref "Q10") (pin "3") (pintype "passive"))
      (node (ref "Q15") (pin "5") (pinfunction "D_5") (pintype "passive"))
      (node (ref "Q16") (pin "5") (pinfunction "D_5") (pintype "passive"))
      (node (ref "Q9") (pin "1") (pinfunction "S_1") (pintype "passive"))
      (node (ref "Q9") (pin "2") (pintype "passive"))
      (node (ref "Q9") (pin "3") (pintype "passive"))
      (node (ref "U25") (pin "2") (pinfunction "2_2") (pintype "passive"))
    )
    (net (code "14") (name "/M1_SH_C") (class "Default")
      (node (ref "Q11") (pin "1") (pinfunction "S_1") (pintype "passive"))
      (node (ref "Q11") (pin "2") (pintype "passive"))
      (node (ref "Q11") (pin "3") (pintype "passive"))
      (node (ref "Q12") (pin "1") (pinfunction "S_1") (pintype "passive"))
      (node (ref "Q12") (pin "2") (pintype "passive"))
      (node (ref "Q12") (pin "3") (pintype "passive"))
      (node (ref "Q17") (pin "5") (pinfunction "D_5") (pintype "passive"))
      (node (ref "Q18") (pin "5") (pinfunction "D_5") (pintype "passive"))
      (node (ref "U25") (pin "1") (pinfunction "1_1") (pintype "passive"))
    )
    (net (code "15") (name "/M1_SL_A") (class "Default")
      (node (ref "J4") (pin "1") (pinfunction "1_1") (pintype "passive"))
      (node (ref "Q13") (pin "1") (pinfunction "S_1") (pintype "passive"))
      (node (ref "Q13") (pin "2") (pintype "passive"))
      (node (ref "Q13") (pin "3") (pintype "passive"))
      (node (ref "Q14") (pin "1") (pinfunction "S_1") (pintype "passive"))
      (node (ref "Q14") (pin "2") (pintype "passive"))
      (node (ref "Q14") (pin "3") (pintype "passive"))
      (node (ref "R83") (pin "2") (pinfunction "2_2") (pintype "passive"))
    )
    (net (code "16") (name "/M1_SL_B") (class "Default")
      (node (ref "J5") (pin "1") (pinfunction "1_1") (pintype "passive"))
      (node (ref "Q15") (pin "1") (pinfunction "S_1") (pintype "passive"))
      (node (ref "Q15") (pin "2") (pintype "passive"))
      (node (ref "Q15") (pin "3") (pintype "passive"))
      (node (ref "Q16") (pin "1") (pinfunction "S_1") (pintype "passive"))
      (node (ref "Q16") (pin "2") (pintype "passive"))
      (node (ref "Q16") (pin "3") (pintype "passive"))
      (node (ref "R84") (pin "2") (pinfunction "2_2") (pintype "passive"))
    )
    (net (code "17") (name "/M1_SL_C") (class "Default")
      (node (ref "J3") (pin "1") (pinfunction "1_1") (pintype "passive"))
    )
    (net (code "18") (name "/M2_A_ISENSE_N") (class "Default")
      (node (ref "C121") (pin "2") (pinfunction "2_2") (pintype "passive"))
      (node (ref "J11") (pin "2") (pinfunction "2_2") (pintype "passive"))
    )
    (net (code "19") (name "/M2_A_ISENSE_P") (class "Default")
      (node (ref "C121") (pin "1") (pinfunction "1_1") (pintype "passive"))
      (node (ref "J9") (pin "2") (pinfunction "2_2") (pintype "passive"))
    )
    (net (code "20") (name "/M2_B_ISENSE_N") (class "Default")
      (node (ref "C122") (pin "2") (pinfunction "2_2") (pintype "passive"))
      (node (ref "J12") (pin "2") (pinfunction "2_2") (pintype "passive"))
    )
    (net (code "21") (name "/M2_B_ISENSE_P") (class "Default")
      (node (ref "C122") (pin "1") (pinfunction "1_1") (pintype "passive"))
      (node (ref "J10") (pin "2") (pinfunction "2_2") (pintype "passive"))
    )
    (net (code "22") (name "/M2_GH_A") (class "Default")
      (node (ref "D24") (pin "1") (pinfunction "C_1") (pintype "passive"))
      (node (ref "R85") (pin "1") (pinfunction "1_1") (pintype "passive"))
    )
    (net (code "23") (name "/M2_GH_B") (class "Default")
      (node (ref "D25") (pin "1") (pinfunction "C_1") (pintype "passive"))
      (node (ref "R86") (pin "1") (pinfunction "1_1") (pintype "passive"))
    )
    (net (code "24") (name "/M2_GH_C") (class "Default")
      (node (ref "D26") (pin "1") (pinfunction "C_1") (pintype "passive"))
      (node (ref "R87") (pin "1") (pinfunction "1_1") (pintype "passive"))
    )
    (net (code "25") (name "/M2_GL_A") (class "Default")
      (node (ref "D29") (pin "1") (pinfunction "C_1") (pintype "passive"))
      (node (ref "R90") (pin "1") (pinfunction "1_1") (pintype "passive"))
    )
    (net (code "26") (name "/M2_GL_B") (class "Default")
      (node (ref "D27") (pin "1") (pinfunction "C_1") (pintype "passive"))
      (node (ref "R88") (pin "1") (pinfunction "1_1") (pintype "passive"))
    )
    (net (code "27") (name "/M2_GL_C") (class "Default")
      (node (ref "D28") (pin "1") (pinfunction "C_1") (pintype "passive"))
      (node (ref "R89") (pin "1") (pinfunction "1_1") (pintype "passive"))
    )
    (net (code "28") (name "/M2_SH_A") (class "Default")
      (node (ref "Q19") (pin "1") (pinfunction "S_1") (pintype "passive"))
      (node (ref "Q19") (pin "2") (pintype "passive"))
      (node (ref "Q19") (pin "3") (pintype "passive"))
      (node (ref "Q20") (pin "1") (pinfunction "S_1") (pintype "passive"))
      (node (ref "Q20") (pin "2") (pintype "passive"))
      (node (ref "Q20") (pin "3") (pintype "passive"))
      (node (ref "Q25") (pin "5") (pinfunction "D_5") (pintype "passive"))
      (node (ref "Q26") (pin "5") (pinfunction "D_5") (pintype "passive"))
      (node (ref "U26") (pin "3") (pinfunction "3_3") (pintype "passive"))
    )
    (net (code "29") (name "/M2_SH_B") (class "Default")
      (node (ref "Q21") (pin "1") (pinfunction "S_1") (pintype "passive"))
      (node (ref "Q21") (pin "2") (pintype "passive"))
      (node (ref "Q21") (pin "3") (pintype "passive"))
      (node (ref "Q22") (pin "1") (pinfunction "S_1") (pintype "passive"))
      (node (ref "Q22") (pin "2") (pintype "passive"))
      (node (ref "Q22") (pin "3") (pintype "passive"))
      (node (ref "Q27") (pin "5") (pinfunction "D_5") (pintype "passive"))
      (node (ref "Q28") (pin "5") (pinfunction "D_5") (pintype "passive"))
      (node (ref "U26") (pin "2") (pinfunction "2_2") (pintype "passive"))
    )
    (net (code "30") (name "/M2_SH_C") (class "Default")
      (node (ref "Q23") (pin "1") (pinfunction "S_1") (pintype "passive"))
      (node (ref "Q23") (pin "2") (pintype "passive"))
      (node (ref "Q23") (pin "3") (pintype "passive"))
      (node (ref "Q24") (pin "1") (pinfunction "S_1") (pintype "passive"))
      (node (ref "Q24") (pin "2") (pintype "passive"))
      (node (ref "Q24") (pin "3") (pintype "passive"))
      (node (ref "Q29") (pin "5") (pinfunction "D_5") (pintype "passive"))
      (node (ref "Q30") (pin "5") (pinfunction "D_5") (pintype "passive"))
      (node (ref "U26") (pin "1") (pinfunction "1_1") (pintype "passive"))
    )
    (net (code "31") (name "/M2_SL_A") (class "Default")
      (node (ref "J9") (pin "1") (pinfunction "1_1") (pintype "passive"))
      (node (ref "Q25") (pin "1") (pinfunction "S_1") (pintype "passive"))
      (node (ref "Q25") (pin "2") (pintype "passive"))
      (node (ref "Q25") (pin "3") (pintype "passive"))
      (node (ref "Q26") (pin "1") (pinfunction "S_1") (pintype "passive"))
      (node (ref "Q26") (pin "2") (pintype "passive"))
      (node (ref "Q26") (pin "3") (pintype "passive"))
      (node (ref "R91") (pin "2") (pinfunction "2_2") (pintype "passive"))
    )
    (net (code "32") (name "/M2_SL_B") (class "Default")
      (node (ref "J10") (pin "1") (pinfunction "1_1") (pintype "passive"))
      (node (ref "Q27") (pin "1") (pinfunction "S_1") (pintype "passive"))
      (node (ref "Q27") (pin "2") (pintype "passive"))
      (node (ref "Q27") (pin "3") (pintype "passive"))
      (node (ref "Q28") (pin "1") (pinfunction "S_1") (pintype "passive"))
      (node (ref "Q28") (pin "2") (pintype "passive"))
      (node (ref "Q28") (pin "3") (pintype "passive"))
      (node (ref "R92") (pin "2") (pinfunction "2_2") (pintype "passive"))
    )
    (net (code "33") (name "/M2_SL_C") (class "Default")
      (node (ref "J8") (pin "1") (pinfunction "1_1") (pintype "passive"))
    )
    (net (code "34") (name "Net-(D18-A)") (class "Default")
      (node (ref "D18") (pin "2") (pinfunction "A_2") (pintype "passive"))
      (node (ref "Q7") (pin "4") (pinfunction "G_4") (pintype "passive"))
      (node (ref "Q8") (pin "4") (pinfunction "G_4") (pintype "passive"))
      (node (ref "R77") (pin "2") (pinfunction "2_2") (pintype "passive"))
    )
    (net (code "35") (name "Net-(D19-A)") (class "Default")
      (node (ref "D19") (pin "2") (pinfunction "A_2") (pintype "passive"))
      (node (ref "Q10") (pin "4") (pinfunction "G_4") (pintype "passive"))
      (node (ref "Q9") (pin "4") (pinfunction "G_4") (pintype "passive"))
      (node (ref "R78") (pin "2") (pinfunction "2_2") (pintype "passive"))
    )
    (net (code "36") (name "Net-(D20-A)") (class "Default")
      (node (ref "D20") (pin "2") (pinfunction "A_2") (pintype "passive"))
      (node (ref "Q11") (pin "4") (pinfunction "G_4") (pintype "passive"))
      (node (ref "Q12") (pin "4") (pinfunction "G_4") (pintype "passive"))
      (node (ref "R79") (pin "2") (pinfunction "2_2") (pintype "passive"))
    )
    (net (code "37") (name "Net-(D21-A)") (class "Default")
      (node (ref "D21") (pin "2") (pinfunction "A_2") (pintype "passive"))
      (node (ref "Q15") (pin "4") (pinfunction "G_4") (pintype "passive"))
      (node (ref "Q16") (pin "4") (pinfunction "G_4") (pintype "passive"))
      (node (ref "R80") (pin "2") (pinfunction "2_2") (pintype "passive"))
    )
    (net (code "38") (name "Net-(D22-A)") (class "Default")
      (node (ref "D22") (pin "2") (pinfunction "A_2") (pintype "passive"))
      (node (ref "Q17") (pin "4") (pinfunction "G_4") (pintype "passive"))
      (node (ref "Q18") (pin "4") (pinfunction "G_4") (pintype "passive"))
      (node (ref "R81") (pin "2") (pinfunction "2_2") (pintype "passive"))
    )
    (net (code "39") (name "Net-(D23-A)") (class "Default")
      (node (ref "D23") (pin "2") (pinfunction "A_2") (pintype "passive"))
      (node (ref "Q13") (pin "4") (pinfunction "G_4") (pintype "passive"))
      (node (ref "Q14") (pin "4") (pinfunction "G_4") (pintype "passive"))
      (node (ref "R82") (pin "2") (pinfunction "2_2") (pintype "passive"))
    )
    (net (code "40") (name "Net-(D24-A)") (class "Default")
      (node (ref "D24") (pin "2") (pinfunction "A_2") (pintype "passive"))
      (node (ref "Q19") (pin "4") (pinfunction "G_4") (pintype "passive"))
      (node (ref "Q20") (pin "4") (pinfunction "G_4") (pintype "passive"))
      (node (ref "R85") (pin "2") (pinfunction "2_2") (pintype "passive"))
    )
    (net (code "41") (name "Net-(D25-A)") (class "Default")
      (node (ref "D25") (pin "2") (pinfunction "A_2") (pintype "passive"))
      (node (ref "Q21") (pin "4") (pinfunction "G_4") (pintype "passive"))
      (node (ref "Q22") (pin "4") (pinfunction "G_4") (pintype "passive"))
      (node (ref "R86") (pin "2") (pinfunction "2_2") (pintype "passive"))
    )
    (net (code "42") (name "Net-(D26-A)") (class "Default")
      (node (ref "D26") (pin "2") (pinfunction "A_2") (pintype "passive"))
      (node (ref "Q23") (pin "4") (pinfunction "G_4") (pintype "passive"))
      (node (ref "Q24") (pin "4") (pinfunction "G_4") (pintype "passive"))
      (node (ref "R87") (pin "2") (pinfunction "2_2") (pintype "passive"))
    )
    (net (code "43") (name "Net-(D27-A)") (class "Default")
      (node (ref "D27") (pin "2") (pinfunction "A_2") (pintype "passive"))
      (node (ref "Q27") (pin "4") (pinfunction "G_4") (pintype "passive"))
      (node (ref "Q28") (pin "4") (pinfunction "G_4") (pintype "passive"))
      (node (ref "R88") (pin "2") (pinfunction "2_2") (pintype "passive"))
    )
    (net (code "44") (name "Net-(D28-A)") (class "Default")
      (node (ref "D28") (pin "2") (pinfunction "A_2") (pintype "passive"))
      (node (ref "Q29") (pin "4") (pinfunction "G_4") (pintype "passive"))
      (node (ref "Q30") (pin "4") (pinfunction "G_4") (pintype "passive"))
      (node (ref "R89") (pin "2") (pinfunction "2_2") (pintype "passive"))
    )
    (net (code "45") (name "Net-(D29-A)") (class "Default")
      (node (ref "D29") (pin "2") (pinfunction "A_2") (pintype "passive"))
      (node (ref "Q25") (pin "4") (pinfunction "G_4") (pintype "passive"))
      (node (ref "Q26") (pin "4") (pinfunction "G_4") (pintype "passive"))
      (node (ref "R90") (pin "2") (pinfunction "2_2") (pintype "passive"))
    )
    (net (code "46") (name "PGND") (class "Default")
      (node (ref "C113") (pin "2") (pinfunction "2_2") (pintype "passive"))
      (node (ref "C114") (pin "2") (pinfunction "2_2") (pintype "passive"))
      (node (ref "C115") (pin "2") (pinfunction "2_2") (pintype "passive"))
      (node (ref "C118") (pin "2") (pinfunction "2_2") (pintype "passive"))
      (node (ref "C119") (pin "2") (pinfunction "2_2") (pintype "passive"))
      (node (ref "C120") (pin "2") (pinfunction "2_2") (pintype "passive"))
      (node (ref "J11") (pin "1") (pinfunction "1_1") (pintype "passive"))
      (node (ref "J12") (pin "1") (pinfunction "1_1") (pintype "passive"))
      (node (ref "J3") (pin "2") (pinfunction "2_2") (pintype "passive"))
      (node (ref "J6") (pin "1") (pinfunction "1_1") (pintype "passive"))
      (node (ref "J7") (pin "1") (pinfunction "1_1") (pintype "passive"))
      (node (ref "J8") (pin "2") (pinfunction "2_2") (pintype "passive"))
      (node (ref "Q17") (pin "1") (pinfunction "S_1") (pintype "passive"))
      (node (ref "Q17") (pin "2") (pintype "passive"))
      (node (ref "Q17") (pin "3") (pintype "passive"))
      (node (ref "Q18") (pin "1") (pinfunction "S_1") (pintype "passive"))
      (node (ref "Q18") (pin "2") (pintype "passive"))
      (node (ref "Q18") (pin "3") (pintype "passive"))
      (node (ref "Q29") (pin "1") (pinfunction "S_1") (pintype "passive"))
      (node (ref "Q29") (pin "2") (pintype "passive"))
      (node (ref "Q29") (pin "3") (pintype "passive"))
      (node (ref "Q30") (pin "1") (pinfunction "S_1") (pintype "passive"))
      (node (ref "Q30") (pin "2") (pintype "passive"))
      (node (ref "Q30") (pin "3") (pintype "passive"))
      (node (ref "R83") (pin "1") (pinfunction "1_1") (pintype "passive"))
      (node (ref "R84") (pin "1") (pinfunction "1_1") (pintype "passive"))
      (node (ref "R91") (pin "1") (pinfunction "1_1") (pintype "passive"))
      (node (ref "R92") (pin "1") (pinfunction "1_1") (pintype "passive"))
    )
    (net (code "47") (name "unconnected-(U25-Pad4)") (class "Default")
      (node (ref "U25") (pin "4") (pinfunction "4_4") (pintype "passive+no_connect"))
    )
    (net (code "48") (name "unconnected-(U25-Pad5)") (class "Default")
      (node (ref "U25") (pin "5") (pinfunction "5_5") (pintype "passive+no_connect"))
    )
    (net (code "49") (name "unconnected-(U26-Pad4)") (class "Default")
      (node (ref "U26") (pin "4") (pinfunction "4_4") (pintype "passive+no_connect"))
    )
    (net (code "50") (name "unconnected-(U26-Pad5)") (class "Default")
      (node (ref "U26") (pin "5") (pinfunction "5_5") (pintype "passive+no_connect"))
    )
  )
)
